# 02_-_HAB.net
KiCad netlist of a schematic drawn in Altium Designer
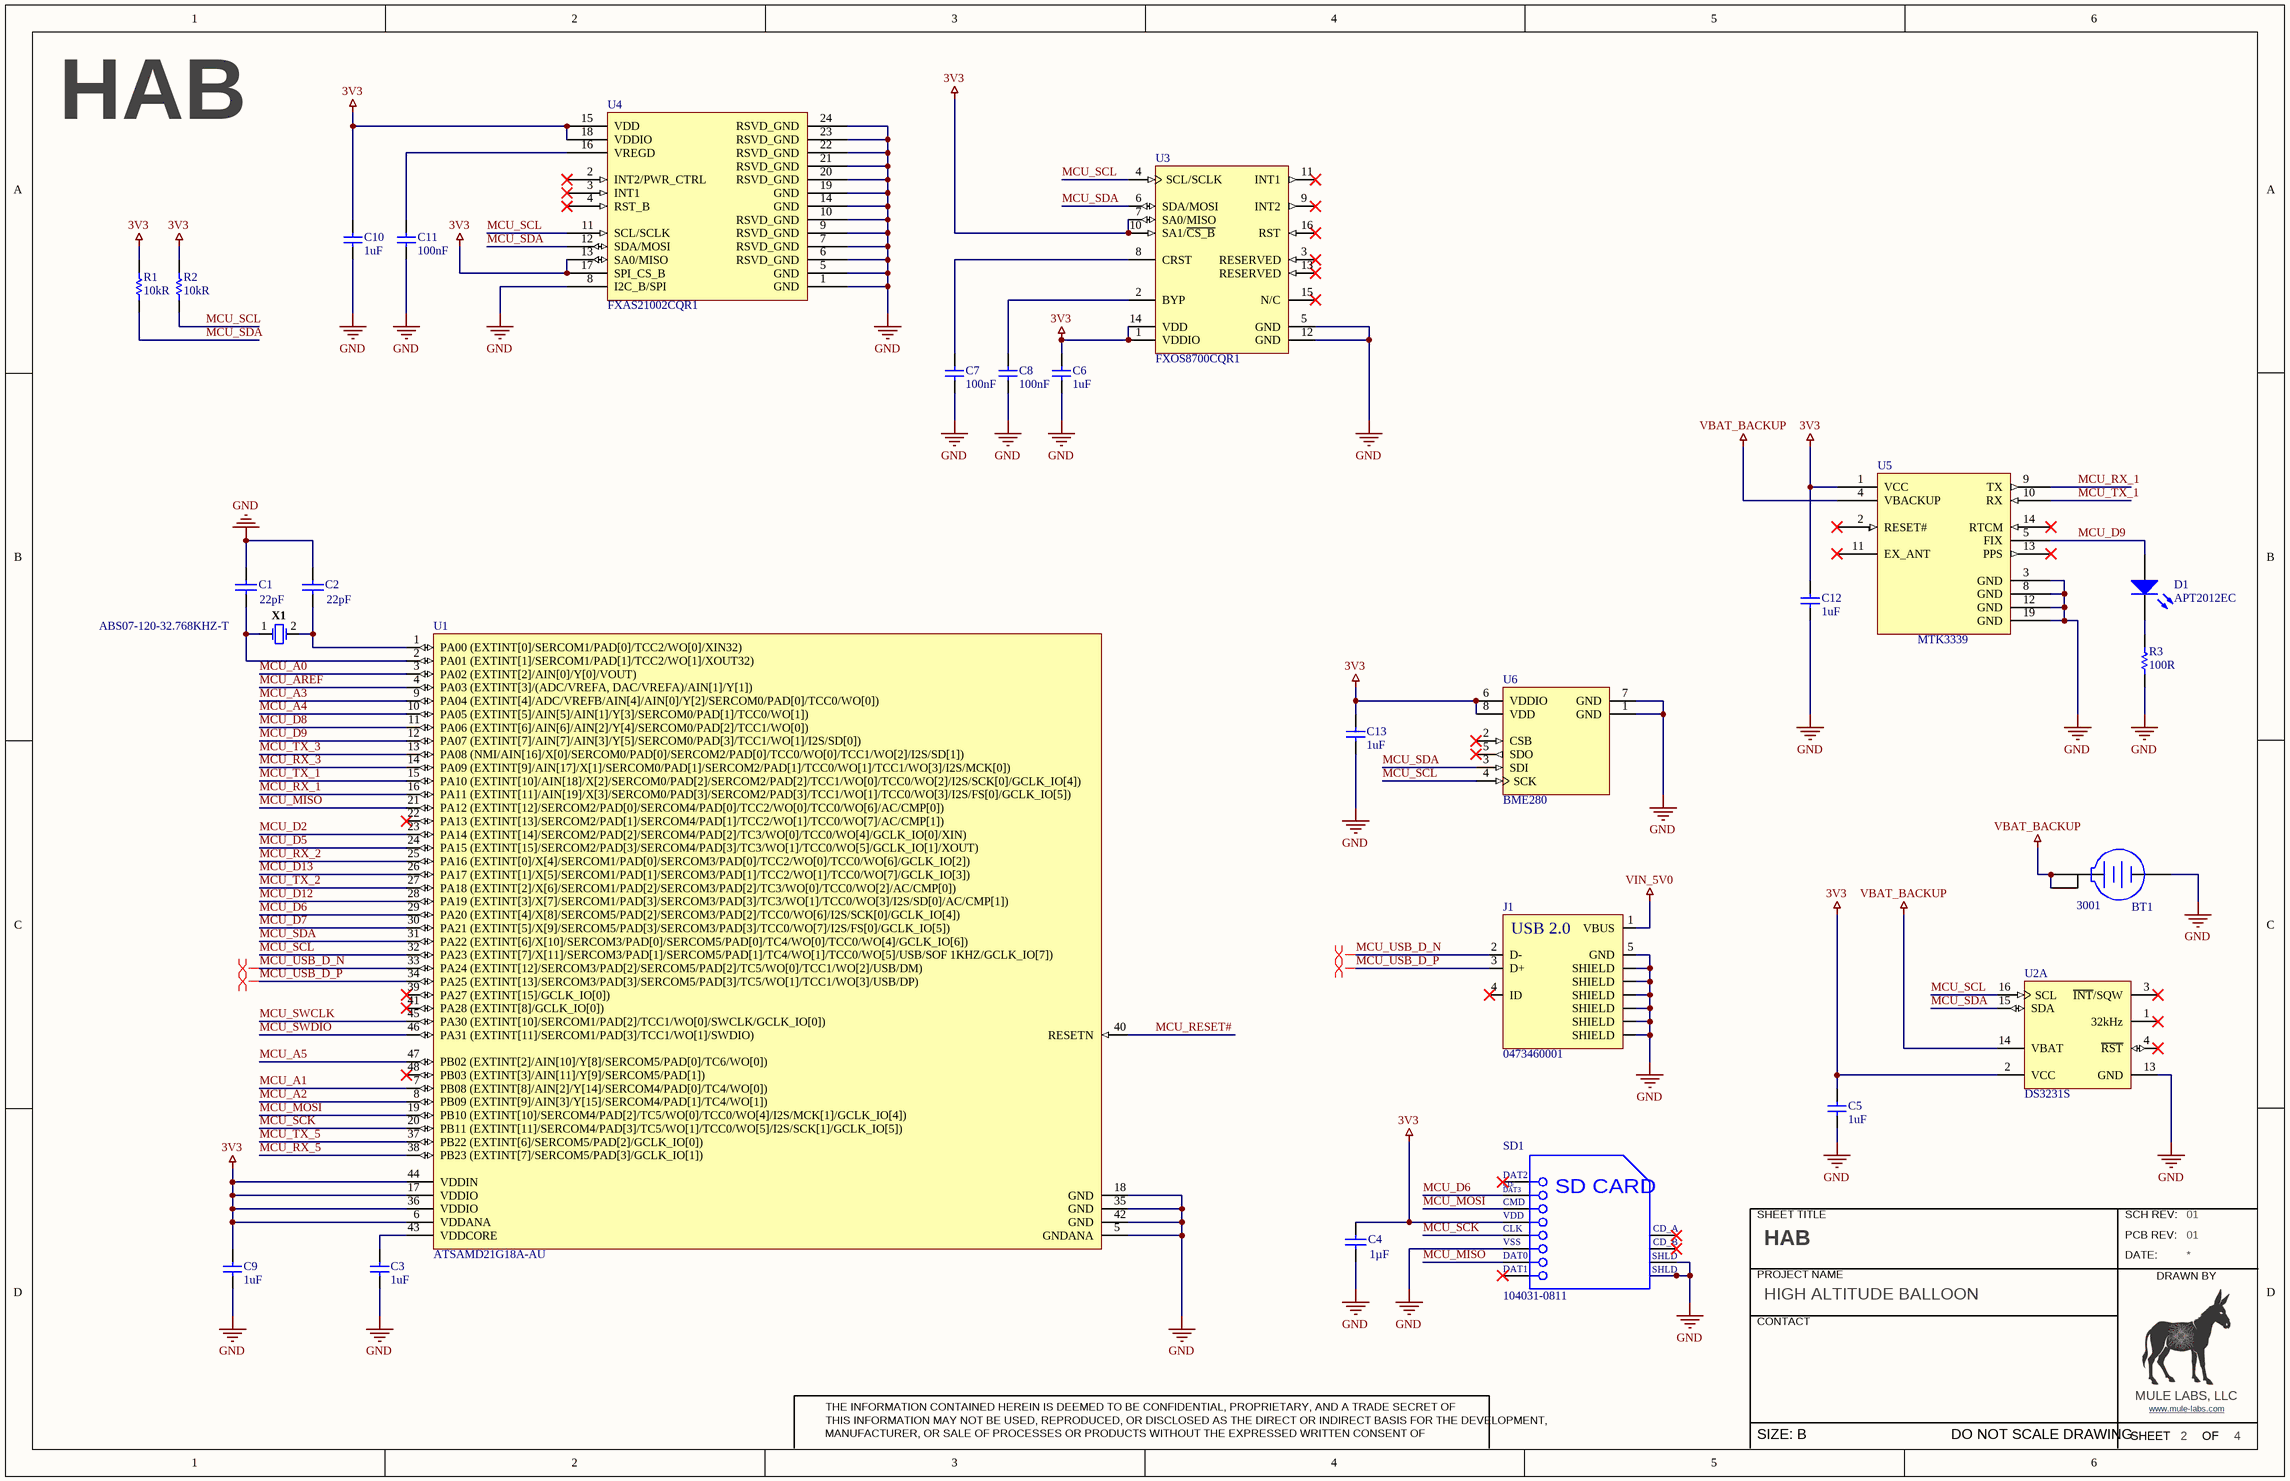
[diagram p0: [02] - HAB.SchDoc]

(export (version "E")
  (design (tool "Eeschema 10.0.6"))
  (components
    (comp (ref "BT1")
      (value "3001")
      (footprint "KSTN-3001_V")
      (description "Holder Battery Coin, 12 mm, 2-Pin THD, RoHS")
      (fields (field (name "MANUFACTURER") "Keystone"))
      (libsource (lib "Altium Content Vault") (part "BATTERY-HOLDER-COIN-3"))
    )
    (comp (ref "C1")
      (value "22pF")
      (footprint "CAPC2013X100X30ML20")
      (fields (field (name "PART NUMBER") "GRM21A5C2E220JW01D") (field (name "MANUFACTURER") "Murata"))
      (libsource (lib "Altium Content Vault") (part "CAP"))
    )
    (comp (ref "C2")
      (value "22pF")
      (footprint "CAPC2013X100X30ML20")
      (fields (field (name "PART NUMBER") "GRM21A5C2E220JW01D") (field (name "MANUFACTURER") "Murata"))
      (libsource (lib "Altium Content Vault") (part "CAP"))
    )
    (comp (ref "C3")
      (value "1uF")
      (footprint "INCH 0805 - METRIC 2012 - H140")
      (description "CAP SMD 1uF 25V 10% 0805")
      (fields
        (field (name "MANUFACTURER") "Murata")
        (field (name "MANUFACTURER PART NUMBER") "GCM21BR71E105KA56L")
      )
      (libsource (lib "Capacitors") (part "GCM21BR71E105KA56L"))
    )
    (comp (ref "C4")
      (value "GRM21BR71C105KA01L")
      (footprint "CAPC2013X135X45ML10T25")
      (fields (field (name "CAPACITANCE") "1µF") (field (name "MANUFACTURER") "Murata"))
      (libsource (lib "Altium Content Vault") (part "CAP-NP-2"))
    )
    (comp (ref "C5")
      (value "1uF")
      (footprint "INCH 0805 - METRIC 2012 - H140")
      (description "CAP SMD 1uF 25V 10% 0805")
      (fields
        (field (name "MANUFACTURER") "Murata")
        (field (name "MANUFACTURER PART NUMBER") "GCM21BR71E105KA56L")
      )
      (libsource (lib "Capacitors") (part "GCM21BR71E105KA56L"))
    )
    (comp (ref "C6")
      (value "1uF")
      (footprint "INCH 0805 - METRIC 2012 - H140")
      (description "CAP SMD 1uF 25V 10% 0805")
      (fields
        (field (name "MANUFACTURER") "Murata")
        (field (name "MANUFACTURER PART NUMBER") "GCM21BR71E105KA56L")
      )
      (libsource (lib "Capacitors") (part "GCM21BR71E105KA56L"))
    )
    (comp (ref "C7")
      (value "100nF")
      (footprint "INCH 0805 - METRIC 2012 - H120")
      (description "CAP CER 0.1UF 100V X7R 0805")
      (fields
        (field (name "MANUFACTURER") "KEMET")
        (field (name "MANUFACTURER PART NUMBER") "C0805C104K1RACTU")
      )
      (libsource (lib "Capacitors") (part "C0805C104K1RACTU"))
    )
    (comp (ref "C8")
      (value "100nF")
      (footprint "INCH 0805 - METRIC 2012 - H120")
      (description "CAP CER 0.1UF 100V X7R 0805")
      (fields
        (field (name "MANUFACTURER") "KEMET")
        (field (name "MANUFACTURER PART NUMBER") "C0805C104K1RACTU")
      )
      (libsource (lib "Capacitors") (part "C0805C104K1RACTU"))
    )
    (comp (ref "C9")
      (value "1uF")
      (footprint "INCH 0805 - METRIC 2012 - H140")
      (description "CAP SMD 1uF 25V 10% 0805")
      (fields
        (field (name "MANUFACTURER") "Murata")
        (field (name "MANUFACTURER PART NUMBER") "GCM21BR71E105KA56L")
      )
      (libsource (lib "Capacitors") (part "GCM21BR71E105KA56L"))
    )
    (comp (ref "C10")
      (value "1uF")
      (footprint "INCH 0805 - METRIC 2012 - H140")
      (description "CAP SMD 1uF 25V 10% 0805")
      (fields
        (field (name "MANUFACTURER") "Murata")
        (field (name "MANUFACTURER PART NUMBER") "GCM21BR71E105KA56L")
      )
      (libsource (lib "Capacitors") (part "GCM21BR71E105KA56L"))
    )
    (comp (ref "C11")
      (value "100nF")
      (footprint "INCH 0805 - METRIC 2012 - H120")
      (description "CAP CER 0.1UF 100V X7R 0805")
      (fields
        (field (name "MANUFACTURER") "KEMET")
        (field (name "MANUFACTURER PART NUMBER") "C0805C104K1RACTU")
      )
      (libsource (lib "Capacitors") (part "C0805C104K1RACTU"))
    )
    (comp (ref "C12")
      (value "1uF")
      (footprint "INCH 0805 - METRIC 2012 - H140")
      (description "CAP SMD 1uF 25V 10% 0805")
      (fields
        (field (name "MANUFACTURER") "Murata")
        (field (name "MANUFACTURER PART NUMBER") "GCM21BR71E105KA56L")
      )
      (libsource (lib "Capacitors") (part "GCM21BR71E105KA56L"))
    )
    (comp (ref "C13")
      (value "1uF")
      (footprint "INCH 0805 - METRIC 2012 - H140")
      (description "CAP SMD 1uF 25V 10% 0805")
      (fields
        (field (name "MANUFACTURER") "Murata")
        (field (name "MANUFACTURER PART NUMBER") "GCM21BR71E105KA56L")
      )
      (libsource (lib "Capacitors") (part "GCM21BR71E105KA56L"))
    )
    (comp (ref "D1")
      (value "APT2012EC")
      (footprint "LED - 0805 - GREEN")
      (description "LED RED CLEAR CHIP SMD")
      (fields (field (name "MANUFACTURER") "Kingbright"))
      (libsource (lib "LEDs") (part "APT2012EC"))
    )
    (comp (ref "J1")
      (value "0473460001")
      (footprint "MOLEX_047346-0001")
      (description "Conn Micro USB Type B RCP 5 POS 0.65mm Solder RA SMD 5 Terminal 1 Port Embossed T/R")
      (fields (field (name "MANUFACTURER") "Molex"))
      (libsource (lib "Connectors") (part "0473460001"))
    )
    (comp (ref "R1")
      (value "10kR")
      (footprint "INCH 0805 - METRIC 2012 - H070")
      (description "RES SMD 10kOHM 1% 1/2W 0805")
      (fields
        (field (name "MANUFACTURER") "Panasonic")
        (field (name "MANUFACTURER PART NUMBER") "ERJ-P06F1002V")
      )
      (libsource (lib "Resistors") (part "ERJ-P06F1002V"))
    )
    (comp (ref "R2")
      (value "10kR")
      (footprint "INCH 0805 - METRIC 2012 - H070")
      (description "RES SMD 10kOHM 1% 1/2W 0805")
      (fields
        (field (name "MANUFACTURER") "Panasonic")
        (field (name "MANUFACTURER PART NUMBER") "ERJ-P06F1002V")
      )
      (libsource (lib "Resistors") (part "ERJ-P06F1002V"))
    )
    (comp (ref "R3")
      (value "100R")
      (footprint "INCH 0805 - METRIC 2012 - H070")
      (description "RES SMD 100 OHM 5% 1/2W 0805")
      (fields
        (field (name "MANUFACTURER") "Panasonic")
        (field (name "MANUFACTURER PART NUMBER") "ERJ-P06J101V")
      )
      (libsource (lib "Resistors") (part "ERJ-P06J101V"))
    )
    (comp (ref "SD1")
      (value "104031-0811")
      (footprint "MOLX-104031-0811_V")
      (description "Micro SD Card, RA, -25 to 85 degC, 8-Pin SMD, RoHS, Tape and Reel")
      (fields (field (name "MANUFACTURER") "Molex"))
      (libsource (lib "Altium Content Vault") (part "CN-SD-8-2SW-2S"))
    )
    (comp (ref "U1")
      (value "ATSAMD21G18A-AU")
      (footprint "ATML-TQFP48_M")
      (fields (field (name "MANUFACTURER") "Atmel"))
      (libsource (lib "Altium Content Vault") (part "ATML-ATSAMD21G18_17_16_15A-TQFP48"))
    )
    (comp (ref "U2")
      (value "DS3231S")
      (footprint "W16-H2_L")
      (description "Extremely Accurate I2C-Integrated Real-Time Clock/TCXO/Crystal, 16-Pin SO, 0 to 70 degC")
      (libsource (lib "Altium Content Vault") (part "MAX-RTC-16-DS3231S-W16#H2"))
    )
    (comp (ref "U3")
      (value "FXOS8700CQR1")
      (footprint "FREE-QFN-16-3000X3000DE_V")
      (fields (field (name "MANUFACTURER") "Freescale"))
      (libsource (lib "Altium Content Vault") (part "FREE-FXOS8700CQR1-16"))
    )
    (comp (ref "U4")
      (value "FXAS21002CQR1")
      (footprint "FXAS21002CQR1")
      (description "NXP Precision 3 Axis Gyro I2C")
      (libsource (lib "ICs - Sensors") (part "FXAS21002CQR1"))
    )
    (comp (ref "U5")
      (value "MTK3339")
      (footprint "MTK3339")
      (description "Ultimate GPS Module 66 channel 10 Hz")
      (libsource (lib "ICs - Sensors") (part "MTK3339"))
    )
    (comp (ref "U6")
      (value "BME280")
      (footprint "BOSC-BME280-8_V")
      (fields (field (name "MANUFACTURER") "Bosch Sensortec"))
      (libsource (lib "Altium Content Vault") (part "BOSC-BME280-8"))
    )
    (comp (ref "X1")
      (value "ABS07-120-32.768KHZ-T")
      (footprint "ABRA-ABS07_A_V")
      (description "Tuning Fork Crystal, 32.768 KHz, +/- 20 ppm, -40 to 85 degC, 2-Pin SMD, RoHS, Tape and Reel")
      (fields (field (name "MANUFACTURER") "Abracon") (field (name "TOLERANCE") "20ppm"))
      (libsource (lib "Altium Content Vault") (part "XTAL-1-2-2"))
    )
  )
  (nets
    (net (code "1") (name "/MCU_A0") (class "Default")
      (node (ref "U1") (pin "3") (pinfunction "PA02_(EXTINT[2]/AIN[0]/Y[0]/VOUT)_3") (pintype "bidirectional"))
    )
    (net (code "2") (name "/MCU_A1") (class "Default")
      (node (ref "U1") (pin "7") (pinfunction "PB08_(EXTINT[8]/AIN[2]/Y[14]/SERCOM4/PAD[0]/TC4/WO[0])_7") (pintype "bidirectional"))
    )
    (net (code "3") (name "/MCU_A2") (class "Default")
      (node (ref "U1") (pin "8") (pinfunction "PB09_(EXTINT[9]/AIN[3]/Y[15]/SERCOM4/PAD[1]/TC4/WO[1])_8") (pintype "bidirectional"))
    )
    (net (code "4") (name "/MCU_A3") (class "Default")
      (node (ref "U1") (pin "9") (pinfunction "PA04_(EXTINT[4]/ADC/VREFB/AIN[4]/AIN[0]/Y[2]/SERCOM0/PAD[0]/TCC0/WO[0])_9") (pintype "bidirectional"))
    )
    (net (code "5") (name "/MCU_A4") (class "Default")
      (node (ref "U1") (pin "10") (pinfunction "PA05_(EXTINT[5]/AIN[5]/AIN[1]/Y[3]/SERCOM0/PAD[1]/TCC0/WO[1])_10") (pintype "bidirectional"))
    )
    (net (code "6") (name "/MCU_A5") (class "Default")
      (node (ref "U1") (pin "47") (pinfunction "PB02_(EXTINT[2]/AIN[10]/Y[8]/SERCOM5/PAD[0]/TC6/WO[0])_47") (pintype "bidirectional"))
    )
    (net (code "7") (name "/MCU_AREF") (class "Default")
      (node (ref "U1") (pin "4") (pinfunction "PA03_(EXTINT[3]/(ADC/VREFA,_DAC/VREFA)/AIN[1]/Y[1])_4") (pintype "bidirectional"))
    )
    (net (code "8") (name "/MCU_D2") (class "Default")
      (node (ref "U1") (pin "23") (pinfunction "PA14_(EXTINT[14]/SERCOM2/PAD[2]/SERCOM4/PAD[2]/TC3/WO[0]/TCC0/WO[4]/GCLK_IO[0]/XIN)_23") (pintype "bidirectional"))
    )
    (net (code "9") (name "/MCU_D5") (class "Default")
      (node (ref "U1") (pin "24") (pinfunction "PA15_(EXTINT[15]/SERCOM2/PAD[3]/SERCOM4/PAD[3]/TC3/WO[1]/TCC0/WO[5]/GCLK_IO[1]/XOUT)_24") (pintype "bidirectional"))
    )
    (net (code "10") (name "/MCU_D6") (class "Default")
      (node (ref "SD1") (pin "2") (pinfunction "CMD_2") (pintype "passive"))
      (node (ref "U1") (pin "29") (pinfunction "PA20_(EXTINT[4]/X[8]/SERCOM5/PAD[2]/SERCOM3/PAD[2]/TCC0/WO[6]/I2S/SCK[0]/GCLK_IO[4])_29") (pintype "bidirectional"))
    )
    (net (code "11") (name "/MCU_D7") (class "Default")
      (node (ref "U1") (pin "30") (pinfunction "PA21_(EXTINT[5]/X[9]/SERCOM5/PAD[3]/SERCOM3/PAD[3]/TCC0/WO[7]/I2S/FS[0]/GCLK_IO[5])_30") (pintype "bidirectional"))
    )
    (net (code "12") (name "/MCU_D8") (class "Default")
      (node (ref "U1") (pin "11") (pinfunction "PA06_(EXTINT[6]/AIN[6]/AIN[2]/Y[4]/SERCOM0/PAD[2]/TCC1/WO[0])_11") (pintype "bidirectional"))
    )
    (net (code "13") (name "/MCU_D9") (class "Default")
      (node (ref "D1") (pin "A") (pintype "passive"))
      (node (ref "U1") (pin "12") (pinfunction "PA07_(EXTINT[7]/AIN[7]/AIN[3]/Y[5]/SERCOM0/PAD[3]/TCC1/WO[1]/I2S/SD[0])_12") (pintype "bidirectional"))
      (node (ref "U5") (pin "5") (pinfunction "FIX_5") (pintype "power_in"))
    )
    (net (code "14") (name "/MCU_D12") (class "Default")
      (node (ref "U1") (pin "28") (pinfunction "PA19_(EXTINT[3]/X[7]/SERCOM1/PAD[3]/SERCOM3/PAD[3]/TC3/WO[1]/TCC0/WO[3]/I2S/SD[0]/AC/CMP[1])_28") (pintype "bidirectional"))
    )
    (net (code "15") (name "/MCU_D13") (class "Default")
      (node (ref "U1") (pin "26") (pinfunction "PA17_(EXTINT[1]/X[5]/SERCOM1/PAD[1]/SERCOM3/PAD[1]/TCC2/WO[1]/TCC0/WO[7]/GCLK_IO[3])_26") (pintype "bidirectional"))
    )
    (net (code "16") (name "/MCU_MISO") (class "Default")
      (node (ref "SD1") (pin "7") (pinfunction "DAT0_7") (pintype "passive"))
      (node (ref "U1") (pin "21") (pinfunction "PA12_(EXTINT[12]/SERCOM2/PAD[0]/SERCOM4/PAD[0]/TCC2/WO[0]/TCC0/WO[6]/AC/CMP[0])_21") (pintype "bidirectional"))
    )
    (net (code "17") (name "/MCU_MOSI") (class "Default")
      (node (ref "SD1") (pin "3") (pinfunction "VSS1_3") (pintype "passive"))
      (node (ref "U1") (pin "19") (pinfunction "PB10_(EXTINT[10]/SERCOM4/PAD[2]/TC5/WO[0]/TCC0/WO[4]/I2S/MCK[1]/GCLK_IO[4])_19") (pintype "bidirectional"))
    )
    (net (code "18") (name "/MCU_RESET#") (class "Default")
      (node (ref "U1") (pin "40") (pinfunction "RESETN_40") (pintype "input"))
    )
    (net (code "19") (name "/MCU_RX_1") (class "Default")
      (node (ref "U1") (pin "16") (pinfunction "PA11_(EXTINT[11]/AIN[19]/X[3]/SERCOM0/PAD[3]/SERCOM2/PAD[3]/TCC1/WO[1]/TCC0/WO[3]/I2S/FS[0]/GCLK_IO[5])_16") (pintype "bidirectional"))
      (node (ref "U5") (pin "9") (pinfunction "TX_9") (pintype "output"))
    )
    (net (code "20") (name "/MCU_RX_2") (class "Default")
      (node (ref "U1") (pin "25") (pinfunction "PA16_(EXTINT[0]/X[4]/SERCOM1/PAD[0]/SERCOM3/PAD[0]/TCC2/WO[0]/TCC0/WO[6]/GCLK_IO[2])_25") (pintype "bidirectional"))
    )
    (net (code "21") (name "/MCU_RX_3") (class "Default")
      (node (ref "U1") (pin "14") (pinfunction "PA09_(EXTINT[9]/AIN[17]/X[1]/SERCOM0/PAD[1]/SERCOM2/PAD[1]/TCC0/WO[1]/TCC1/WO[3]/I2S/MCK[0])_14") (pintype "bidirectional"))
    )
    (net (code "22") (name "/MCU_RX_5") (class "Default")
      (node (ref "U1") (pin "38") (pinfunction "PB23_(EXTINT[7]/SERCOM5/PAD[3]/GCLK_IO[1])_38") (pintype "bidirectional"))
    )
    (net (code "23") (name "/MCU_SCK") (class "Default")
      (node (ref "SD1") (pin "5") (pinfunction "CLK_5") (pintype "passive"))
      (node (ref "U1") (pin "20") (pinfunction "PB11_(EXTINT[11]/SERCOM4/PAD[3]/TC5/WO[1]/TCC0/WO[5]/I2S/SCK[1]/GCLK_IO[5])_20") (pintype "bidirectional"))
    )
    (net (code "24") (name "/MCU_SCL") (class "Default")
      (node (ref "R2") (pin "1") (pintype "passive"))
      (node (ref "U1") (pin "32") (pinfunction "PA23_(EXTINT[7]/X[11]/SERCOM3/PAD[1]/SERCOM5/PAD[1]/TC4/WO[1]/TCC0/WO[5]/USB/SOF_1KHZ/GCLK_IO[7])_32") (pintype "bidirectional"))
      (node (ref "U2") (pin "16") (pinfunction "SCL_16") (pintype "input"))
      (node (ref "U3") (pin "4") (pinfunction "SCL/SCLK_4") (pintype "input"))
      (node (ref "U4") (pin "11") (pinfunction "SCL/SCLK_11") (pintype "input"))
      (node (ref "U6") (pin "4") (pinfunction "SCK_4") (pintype "input"))
    )
    (net (code "25") (name "/MCU_SDA") (class "Default")
      (node (ref "R1") (pin "1") (pintype "passive"))
      (node (ref "U1") (pin "31") (pinfunction "PA22_(EXTINT[6]/X[10]/SERCOM3/PAD[0]/SERCOM5/PAD[0]/TC4/WO[0]/TCC0/WO[4]/GCLK_IO[6])_31") (pintype "bidirectional"))
      (node (ref "U2") (pin "15") (pinfunction "SDA_15") (pintype "bidirectional"))
      (node (ref "U3") (pin "6") (pinfunction "SDA/MOSI_6") (pintype "bidirectional"))
      (node (ref "U4") (pin "12") (pinfunction "SDA/MOSI_12") (pintype "bidirectional"))
      (node (ref "U6") (pin "3") (pinfunction "SDI_3") (pintype "input"))
    )
    (net (code "26") (name "/MCU_SWCLK") (class "Default")
      (node (ref "U1") (pin "45") (pinfunction "PA30_(EXTINT[10]/SERCOM1/PAD[2]/TCC1/WO[0]/SWCLK/GCLK_IO[0])_45") (pintype "bidirectional"))
    )
    (net (code "27") (name "/MCU_SWDIO") (class "Default")
      (node (ref "U1") (pin "46") (pinfunction "PA31_(EXTINT[11]/SERCOM1/PAD[3]/TCC1/WO[1]/SWDIO)_46") (pintype "bidirectional"))
    )
    (net (code "28") (name "/MCU_TX_1") (class "Default")
      (node (ref "U1") (pin "15") (pinfunction "PA10_(EXTINT[10]/AIN[18]/X[2]/SERCOM0/PAD[2]/SERCOM2/PAD[2]/TCC1/WO[0]/TCC0/WO[2]/I2S/SCK[0]/GCLK_IO[4])_15") (pintype "bidirectional"))
      (node (ref "U5") (pin "10") (pinfunction "RX_10") (pintype "input"))
    )
    (net (code "29") (name "/MCU_TX_2") (class "Default")
      (node (ref "U1") (pin "27") (pinfunction "PA18_(EXTINT[2]/X[6]/SERCOM1/PAD[2]/SERCOM3/PAD[2]/TC3/WO[0]/TCC0/WO[2]/AC/CMP[0])_27") (pintype "bidirectional"))
    )
    (net (code "30") (name "/MCU_TX_3") (class "Default")
      (node (ref "U1") (pin "13") (pinfunction "PA08_(NMI/AIN[16]/X[0]/SERCOM0/PAD[0]/SERCOM2/PAD[0]/TCC0/WO[0]/TCC1/WO[2]/I2S/SD[1])_13") (pintype "bidirectional"))
    )
    (net (code "31") (name "/MCU_TX_5") (class "Default")
      (node (ref "U1") (pin "37") (pinfunction "PB22_(EXTINT[6]/SERCOM5/PAD[2]/GCLK_IO[0])_37") (pintype "bidirectional"))
    )
    (net (code "32") (name "/MCU_USB_D_N") (class "Default")
      (node (ref "J1") (pin "2") (pinfunction "D-_2") (pintype "passive"))
      (node (ref "U1") (pin "33") (pinfunction "PA24_(EXTINT[12]/SERCOM3/PAD[2]/SERCOM5/PAD[2]/TC5/WO[0]/TCC1/WO[2]/USB/DM)_33") (pintype "bidirectional"))
    )
    (net (code "33") (name "/MCU_USB_D_P") (class "Default")
      (node (ref "J1") (pin "3") (pinfunction "D+_3") (pintype "passive"))
      (node (ref "U1") (pin "34") (pinfunction "PA25_(EXTINT[13]/SERCOM3/PAD[3]/SERCOM5/PAD[3]/TC5/WO[1]/TCC1/WO[3]/USB/DP)_34") (pintype "bidirectional"))
    )
    (net (code "34") (name "3V3") (class "Default")
      (node (ref "C10") (pin "2") (pintype "passive"))
      (node (ref "C12") (pin "2") (pintype "passive"))
      (node (ref "C13") (pin "2") (pintype "passive"))
      (node (ref "C4") (pin "1") (pinfunction "1_1") (pintype "passive"))
      (node (ref "C5") (pin "2") (pintype "passive"))
      (node (ref "C6") (pin "2") (pintype "passive"))
      (node (ref "C9") (pin "2") (pintype "passive"))
      (node (ref "R1") (pin "2") (pintype "passive"))
      (node (ref "R2") (pin "2") (pintype "passive"))
      (node (ref "SD1") (pin "4") (pinfunction "VDD_4") (pintype "passive"))
      (node (ref "U1") (pin "17") (pinfunction "VDDIO_17") (pintype "power_in"))
      (node (ref "U1") (pin "36") (pinfunction "VDDIO_36") (pintype "power_in"))
      (node (ref "U1") (pin "44") (pinfunction "VDDIN_44") (pintype "power_in"))
      (node (ref "U1") (pin "6") (pinfunction "VDDANA_6") (pintype "power_in"))
      (node (ref "U2") (pin "2") (pinfunction "VCC_2") (pintype "power_in"))
      (node (ref "U3") (pin "1") (pinfunction "VDDIO_1") (pintype "power_in"))
      (node (ref "U3") (pin "10") (pinfunction "SA1/~{CS_B}_10") (pintype "input"))
      (node (ref "U3") (pin "14") (pinfunction "VDD_14") (pintype "power_in"))
      (node (ref "U3") (pin "7") (pinfunction "SA0/MISO_7") (pintype "bidirectional"))
      (node (ref "U4") (pin "13") (pinfunction "SA0/MISO_13") (pintype "bidirectional"))
      (node (ref "U4") (pin "15") (pinfunction "VDD_15") (pintype "power_in"))
      (node (ref "U4") (pin "17") (pinfunction "SPI_CS_B_17") (pintype "power_in"))
      (node (ref "U4") (pin "18") (pinfunction "VDDIO_18") (pintype "power_in"))
      (node (ref "U5") (pin "1") (pinfunction "VCC_1") (pintype "power_in"))
      (node (ref "U6") (pin "6") (pinfunction "VDDIO_6") (pintype "power_in"))
      (node (ref "U6") (pin "8") (pinfunction "VDD_8") (pintype "power_in"))
    )
    (net (code "35") (name "GND") (class "Default")
      (node (ref "BT1") (pin "3") (pinfunction "-_3") (pintype "passive"))
      (node (ref "C1") (pin "2") (pinfunction "2_2") (pintype "passive"))
      (node (ref "C10") (pin "1") (pintype "passive"))
      (node (ref "C11") (pin "1") (pintype "passive"))
      (node (ref "C12") (pin "1") (pintype "passive"))
      (node (ref "C13") (pin "1") (pintype "passive"))
      (node (ref "C2") (pin "2") (pinfunction "2_2") (pintype "passive"))
      (node (ref "C3") (pin "1") (pintype "passive"))
      (node (ref "C4") (pin "2") (pinfunction "2_2") (pintype "passive"))
      (node (ref "C5") (pin "1") (pintype "passive"))
      (node (ref "C6") (pin "1") (pintype "passive"))
      (node (ref "C7") (pin "1") (pintype "passive"))
      (node (ref "C8") (pin "1") (pintype "passive"))
      (node (ref "C9") (pin "1") (pintype "passive"))
      (node (ref "J1") (pin "0") (pinfunction "SHIELD_0") (pintype "passive"))
      (node (ref "J1") (pin "5") (pinfunction "GND_5") (pintype "passive"))
      (node (ref "R3") (pin "1") (pintype "passive"))
      (node (ref "SD1") (pin "11") (pinfunction "SHLD1_11") (pintype "passive"))
      (node (ref "SD1") (pin "12") (pinfunction "SHLD2_12") (pintype "passive"))
      (node (ref "SD1") (pin "6") (pinfunction "VSS2_6") (pintype "passive"))
      (node (ref "U1") (pin "18") (pinfunction "GND_18") (pintype "power_in"))
      (node (ref "U1") (pin "35") (pinfunction "GND_35") (pintype "power_in"))
      (node (ref "U1") (pin "42") (pinfunction "GND_42") (pintype "power_in"))
      (node (ref "U1") (pin "5") (pinfunction "GNDANA_5") (pintype "power_in"))
      (node (ref "U2") (pin "13") (pinfunction "GND_13") (pintype "power_in"))
      (node (ref "U3") (pin "12") (pinfunction "GND_12") (pintype "power_in"))
      (node (ref "U3") (pin "5") (pinfunction "GND_5") (pintype "power_in"))
      (node (ref "U4") (pin "1") (pinfunction "GND_1") (pintype "power_in"))
      (node (ref "U4") (pin "10") (pinfunction "RSVD_GND_10") (pintype "power_in"))
      (node (ref "U4") (pin "14") (pinfunction "GND_14") (pintype "power_in"))
      (node (ref "U4") (pin "19") (pinfunction "GND_19") (pintype "power_in"))
      (node (ref "U4") (pin "20") (pinfunction "RSVD_GND_20") (pintype "power_in"))
      (node (ref "U4") (pin "21") (pinfunction "RSVD_GND_21") (pintype "power_in"))
      (node (ref "U4") (pin "22") (pinfunction "RSVD_GND_22") (pintype "power_in"))
      (node (ref "U4") (pin "23") (pinfunction "RSVD_GND_23") (pintype "power_in"))
      (node (ref "U4") (pin "24") (pinfunction "RSVD_GND_24") (pintype "power_in"))
      (node (ref "U4") (pin "5") (pinfunction "GND_5") (pintype "power_in"))
      (node (ref "U4") (pin "6") (pinfunction "RSVD_GND_6") (pintype "power_in"))
      (node (ref "U4") (pin "7") (pinfunction "RSVD_GND_7") (pintype "power_in"))
      (node (ref "U4") (pin "8") (pinfunction "I2C_B/SPI_8") (pintype "power_in"))
      (node (ref "U4") (pin "9") (pinfunction "RSVD_GND_9") (pintype "power_in"))
      (node (ref "U5") (pin "12") (pinfunction "GND_12") (pintype "power_in"))
      (node (ref "U5") (pin "19") (pinfunction "GND_19") (pintype "power_in"))
      (node (ref "U5") (pin "3") (pinfunction "GND_3") (pintype "power_in"))
      (node (ref "U5") (pin "8") (pinfunction "GND_8") (pintype "power_in"))
      (node (ref "U6") (pin "1") (pinfunction "GND_1") (pintype "power_in"))
      (node (ref "U6") (pin "7") (pinfunction "GND_7") (pintype "power_in"))
    )
    (net (code "36") (name "Net-(D1-PadC)") (class "Default")
      (node (ref "D1") (pin "C") (pintype "passive"))
      (node (ref "R3") (pin "2") (pintype "passive"))
    )
    (net (code "37") (name "Net-(U1-PA00_(EXTINT[0]{slash}SERCOM1{slash}PAD[0]{slash}TCC2{slash}WO[0]{slash}XIN32))") (class "Default")
      (node (ref "C2") (pin "1") (pinfunction "1_1") (pintype "passive"))
      (node (ref "U1") (pin "1") (pinfunction "PA00_(EXTINT[0]/SERCOM1/PAD[0]/TCC2/WO[0]/XIN32)_1") (pintype "bidirectional"))
      (node (ref "X1") (pin "2") (pinfunction "2_2") (pintype "passive"))
    )
    (net (code "38") (name "Net-(U1-PA01_(EXTINT[1]{slash}SERCOM1{slash}PAD[1]{slash}TCC2{slash}WO[1]{slash}XOUT32))") (class "Default")
      (node (ref "C1") (pin "1") (pinfunction "1_1") (pintype "passive"))
      (node (ref "U1") (pin "2") (pinfunction "PA01_(EXTINT[1]/SERCOM1/PAD[1]/TCC2/WO[1]/XOUT32)_2") (pintype "bidirectional"))
      (node (ref "X1") (pin "1") (pinfunction "1_1") (pintype "passive"))
    )
    (net (code "39") (name "Net-(U1-VDDCORE)") (class "Default")
      (node (ref "C3") (pin "2") (pintype "passive"))
      (node (ref "U1") (pin "43") (pinfunction "VDDCORE_43") (pintype "power_in"))
    )
    (net (code "40") (name "Net-(U3-BYP)") (class "Default")
      (node (ref "C8") (pin "2") (pintype "passive"))
      (node (ref "U3") (pin "2") (pinfunction "BYP_2") (pintype "passive"))
    )
    (net (code "41") (name "Net-(U3-CRST)") (class "Default")
      (node (ref "C7") (pin "2") (pintype "passive"))
      (node (ref "U3") (pin "8") (pinfunction "CRST_8") (pintype "passive"))
    )
    (net (code "42") (name "Net-(U4-VREGD)") (class "Default")
      (node (ref "C11") (pin "2") (pintype "passive"))
      (node (ref "U4") (pin "16") (pinfunction "VREGD_16") (pintype "power_in"))
    )
    (net (code "43") (name "VBAT_BACKUP") (class "Default")
      (node (ref "BT1") (pin "1") (pinfunction "+_1") (pintype "passive"))
      (node (ref "BT1") (pin "2") (pinfunction "+_2") (pintype "passive"))
      (node (ref "U2") (pin "14") (pinfunction "VBAT_14") (pintype "power_in"))
      (node (ref "U5") (pin "4") (pinfunction "VBACKUP_4") (pintype "power_in"))
    )
    (net (code "44") (name "VIN_5V0") (class "Default")
      (node (ref "J1") (pin "1") (pinfunction "VBUS_1") (pintype "passive"))
    )
    (net (code "45") (name "unconnected-(J1-ID-Pad4)") (class "Default")
      (node (ref "J1") (pin "4") (pinfunction "ID_4") (pintype "passive+no_connect"))
    )
    (net (code "46") (name "unconnected-(SD1-CD_A-Pad9)") (class "Default")
      (node (ref "SD1") (pin "9") (pinfunction "CD_A_9") (pintype "passive+no_connect"))
    )
    (net (code "47") (name "unconnected-(SD1-CD_B-Pad10)") (class "Default")
      (node (ref "SD1") (pin "10") (pinfunction "CD_B_10") (pintype "passive+no_connect"))
    )
    (net (code "48") (name "unconnected-(SD1-CD{slash}DAT3-Pad1)") (class "Default")
      (node (ref "SD1") (pin "1") (pinfunction "CD/DAT3_1") (pintype "passive+no_connect"))
    )
    (net (code "49") (name "unconnected-(SD1-DAT1-Pad8)") (class "Default")
      (node (ref "SD1") (pin "8") (pinfunction "DAT1_8") (pintype "passive+no_connect"))
    )
    (net (code "50") (name "unconnected-(U1-PA13_(EXTINT[13]{slash}SERCOM2{slash}PAD[1]{slash}SERCOM4{slash}PAD[1]{slash}TCC2{slash}WO[1]{slash}TCC0{slash}WO[7]{slash}AC{slash}CMP[1])-Pad22)") (class "Default")
      (node (ref "U1") (pin "22") (pinfunction "PA13_(EXTINT[13]/SERCOM2/PAD[1]/SERCOM4/PAD[1]/TCC2/WO[1]/TCC0/WO[7]/AC/CMP[1])_22") (pintype "bidirectional+no_connect"))
    )
    (net (code "51") (name "unconnected-(U1-PA27_(EXTINT[15]{slash}GCLK_IO[0])-Pad39)") (class "Default")
      (node (ref "U1") (pin "39") (pinfunction "PA27_(EXTINT[15]/GCLK_IO[0])_39") (pintype "bidirectional+no_connect"))
    )
    (net (code "52") (name "unconnected-(U1-PA28_(EXTINT[8]{slash}GCLK_IO[0])-Pad41)") (class "Default")
      (node (ref "U1") (pin "41") (pinfunction "PA28_(EXTINT[8]/GCLK_IO[0])_41") (pintype "bidirectional+no_connect"))
    )
    (net (code "53") (name "unconnected-(U1-PB03_(EXTINT[3]{slash}AIN[11]{slash}Y[9]{slash}SERCOM5{slash}PAD[1])-Pad48)") (class "Default")
      (node (ref "U1") (pin "48") (pinfunction "PB03_(EXTINT[3]/AIN[11]/Y[9]/SERCOM5/PAD[1])_48") (pintype "bidirectional+no_connect"))
    )
    (net (code "54") (name "unconnected-(U2A-32kHz-Pad1)") (class "Default")
      (node (ref "U2") (pin "1") (pinfunction "32kHz_1") (pintype "open_collector+no_connect"))
    )
    (net (code "55") (name "unconnected-(U2A-~{INT}{slash}SQW-Pad3)") (class "Default")
      (node (ref "U2") (pin "3") (pinfunction "~{INT}/SQW_3") (pintype "open_collector+no_connect"))
    )
    (net (code "56") (name "unconnected-(U2A-~{RST}-Pad4)") (class "Default")
      (node (ref "U2") (pin "4") (pinfunction "~{RST}_4") (pintype "bidirectional+no_connect"))
    )
    (net (code "57") (name "unconnected-(U3-INT1-Pad11)") (class "Default")
      (node (ref "U3") (pin "11") (pinfunction "INT1_11") (pintype "output+no_connect"))
    )
    (net (code "58") (name "unconnected-(U3-INT2-Pad9)") (class "Default")
      (node (ref "U3") (pin "9") (pinfunction "INT2_9") (pintype "output+no_connect"))
    )
    (net (code "59") (name "unconnected-(U3-N{slash}C-Pad15)") (class "Default")
      (node (ref "U3") (pin "15") (pinfunction "N/C_15") (pintype "passive+no_connect"))
    )
    (net (code "60") (name "unconnected-(U3-RESERVED-Pad3)") (class "Default")
      (node (ref "U3") (pin "3") (pinfunction "RESERVED_3") (pintype "input+no_connect"))
    )
    (net (code "61") (name "unconnected-(U3-RESERVED-Pad13)") (class "Default")
      (node (ref "U3") (pin "13") (pinfunction "RESERVED_13") (pintype "input+no_connect"))
    )
    (net (code "62") (name "unconnected-(U3-RST-Pad16)") (class "Default")
      (node (ref "U3") (pin "16") (pinfunction "RST_16") (pintype "input+no_connect"))
    )
    (net (code "63") (name "unconnected-(U4-INT1-Pad3)") (class "Default")
      (node (ref "U4") (pin "3") (pinfunction "INT1_3") (pintype "input+no_connect"))
    )
    (net (code "64") (name "unconnected-(U4-INT2{slash}PWR_CTRL-Pad2)") (class "Default")
      (node (ref "U4") (pin "2") (pinfunction "INT2/PWR_CTRL_2") (pintype "input+no_connect"))
    )
    (net (code "65") (name "unconnected-(U4-RST_B-Pad4)") (class "Default")
      (node (ref "U4") (pin "4") (pinfunction "RST_B_4") (pintype "input+no_connect"))
    )
    (net (code "66") (name "unconnected-(U5-EX_ANT-Pad11)") (class "Default")
      (node (ref "U5") (pin "11") (pinfunction "EX_ANT_11") (pintype "passive+no_connect"))
    )
    (net (code "67") (name "unconnected-(U5-PPS-Pad13)") (class "Default")
      (node (ref "U5") (pin "13") (pinfunction "PPS_13") (pintype "output+no_connect"))
    )
    (net (code "68") (name "unconnected-(U5-RESET#-Pad2)") (class "Default")
      (node (ref "U5") (pin "2") (pinfunction "RESET#_2") (pintype "input+no_connect"))
    )
    (net (code "69") (name "unconnected-(U5-RTCM-Pad14)") (class "Default")
      (node (ref "U5") (pin "14") (pinfunction "RTCM_14") (pintype "input+no_connect"))
    )
    (net (code "70") (name "unconnected-(U6-CSB-Pad2)") (class "Default")
      (node (ref "U6") (pin "2") (pinfunction "CSB_2") (pintype "input+no_connect"))
    )
    (net (code "71") (name "unconnected-(U6-SDO-Pad5)") (class "Default")
      (node (ref "U6") (pin "5") (pinfunction "SDO_5") (pintype "output+no_connect"))
    )
  )
)
